# pedal.net
KiCad netlist of a schematic drawn in EAGLE
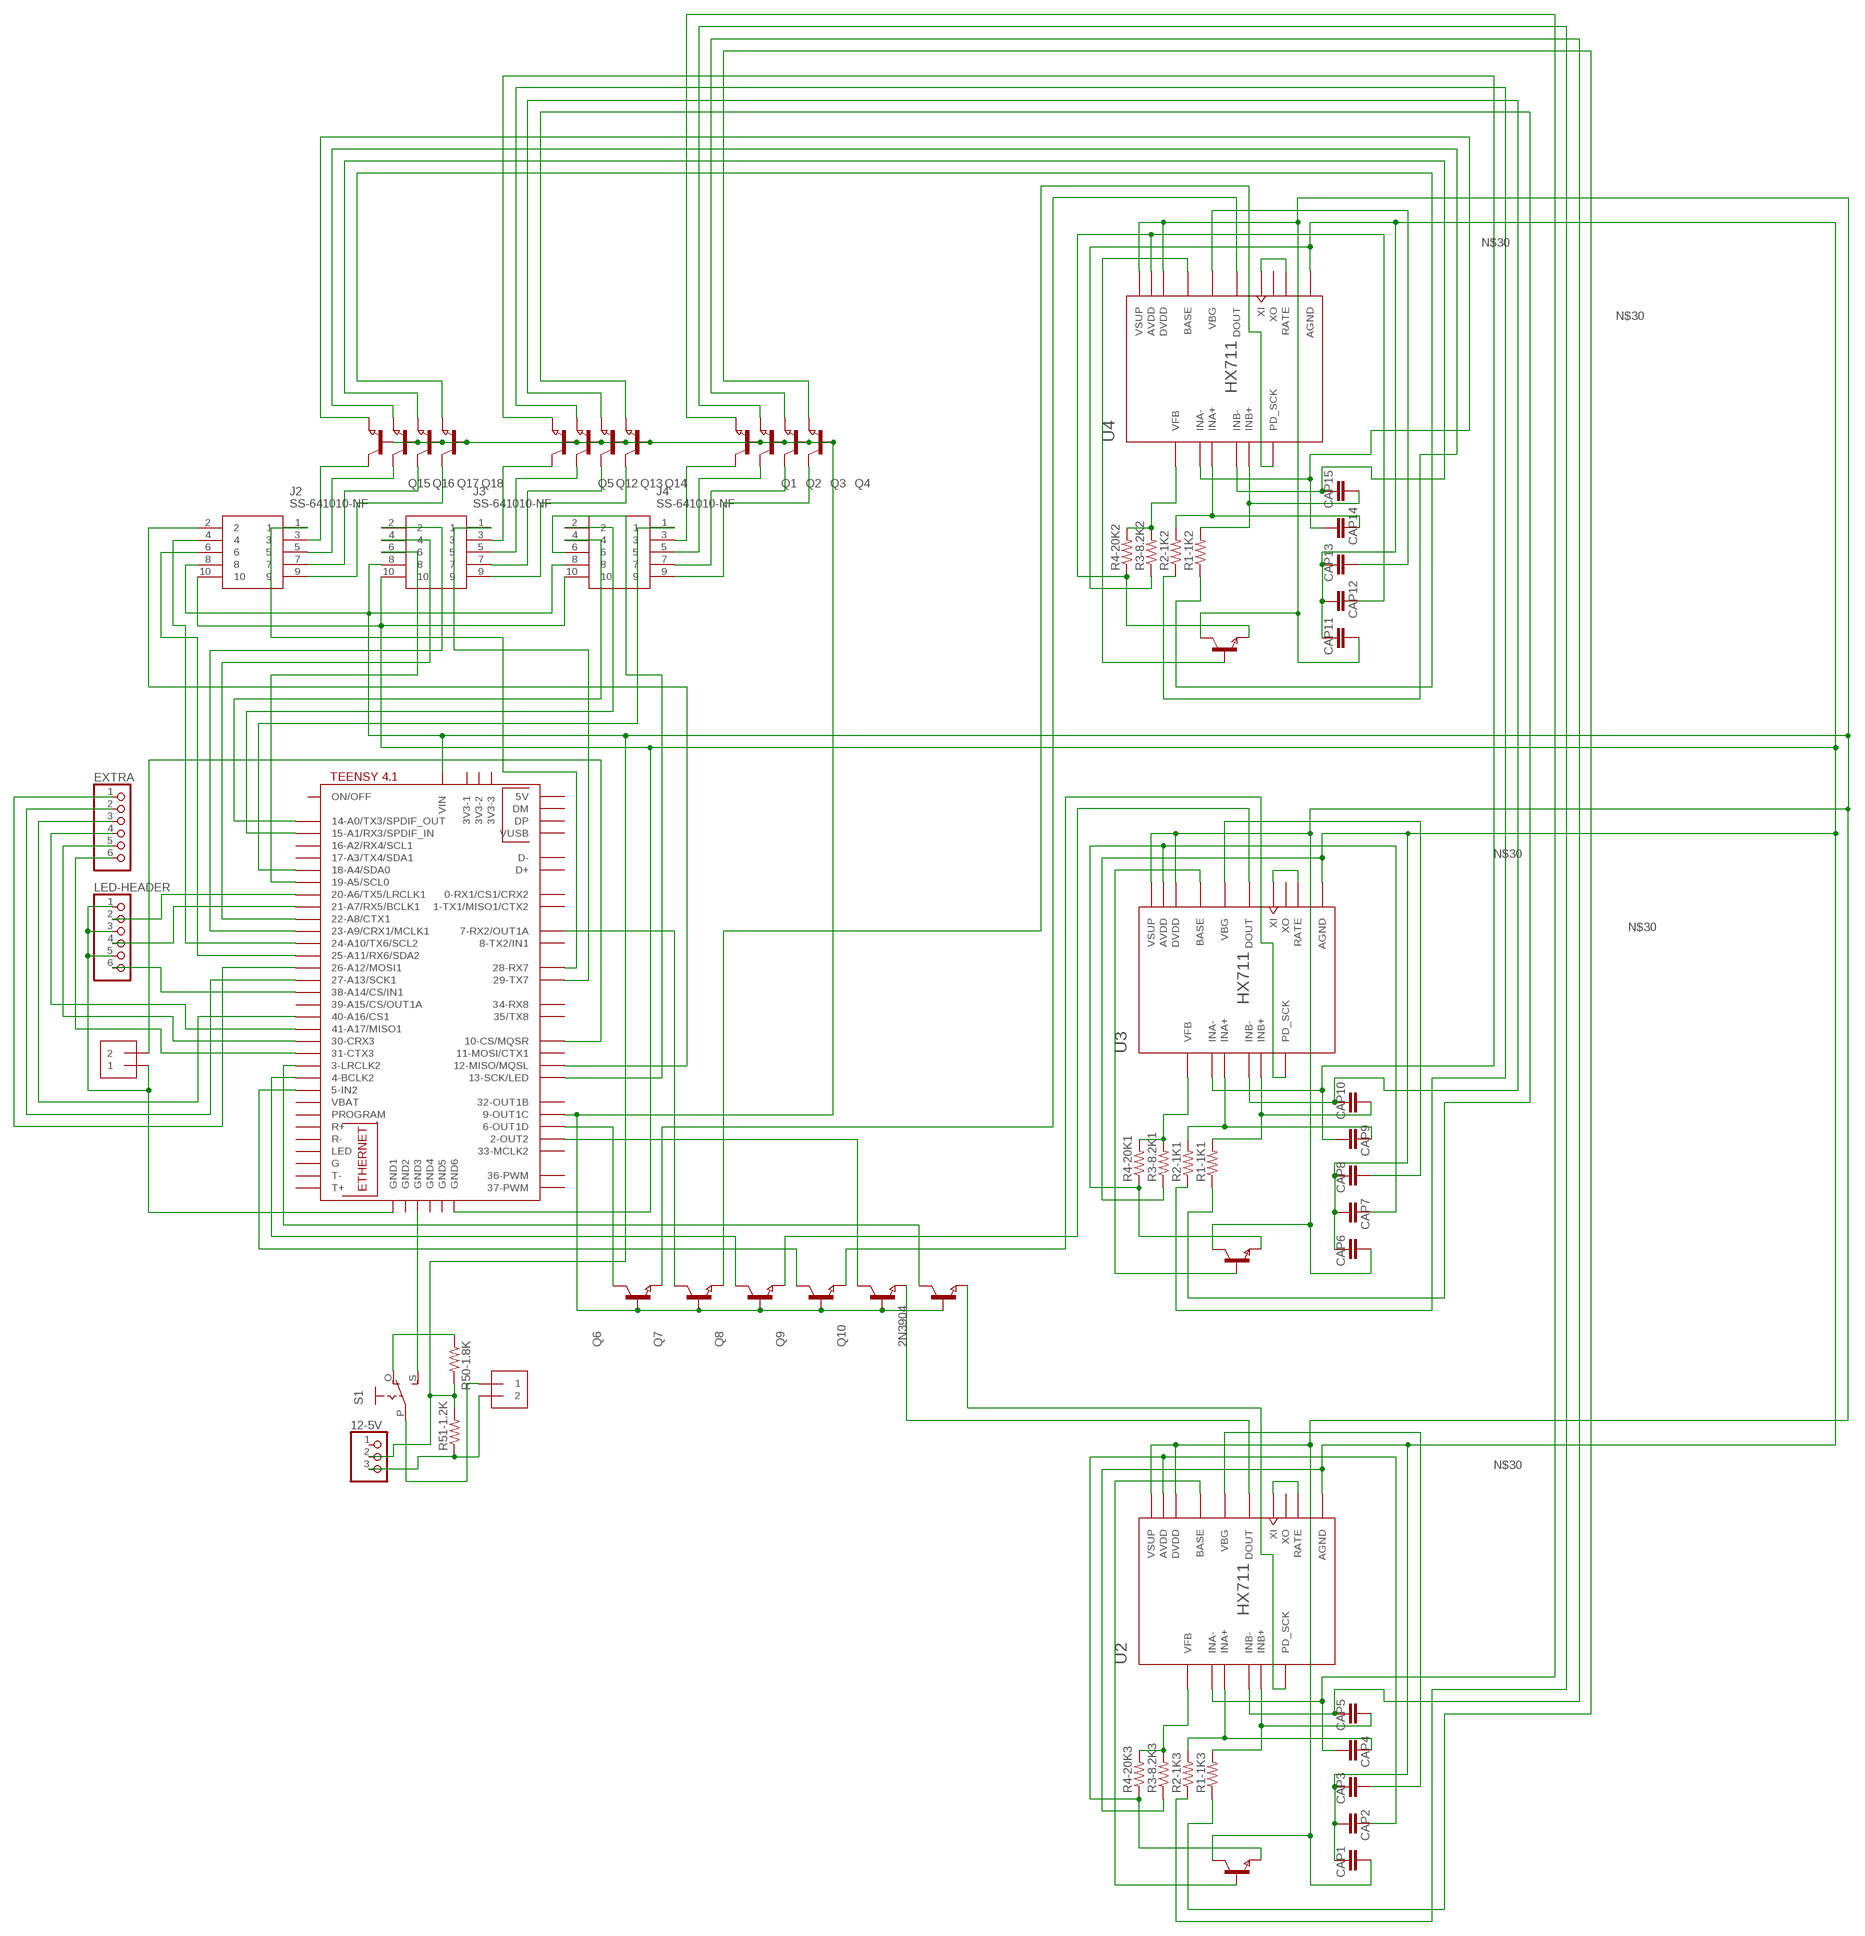
[diagram p0: schematic, sheet 1]

(export (version "E")
  (design (tool "Eeschema 10.0.6"))
  (components
    (comp (ref "2N3904")
      (value "NPN-TRANSISTOR_SOT23")
      (footprint "eagle-import:SOT23")
      (libsource (lib "eagle-import") (part "NPN-TRANSISTOR_SOT23"))
    )
    (comp (ref "12-5V")
      (value "PINHD-1X3")
      (footprint "eagle-import:1X03")
      (libsource (lib "eagle-import") (part "PINHD-1X3"))
    )
    (comp (ref "CAP1")
      (value "1uf")
      (footprint "eagle-import:0603")
      (libsource (lib "eagle-import") (part "10NF-0603-50V-10%"))
    )
    (comp (ref "CAP2")
      (value "1uf")
      (footprint "eagle-import:0603")
      (libsource (lib "eagle-import") (part "10NF-0603-50V-10%"))
    )
    (comp (ref "CAP3")
      (value "1uf")
      (footprint "eagle-import:0603")
      (libsource (lib "eagle-import") (part "10NF-0603-50V-10%"))
    )
    (comp (ref "CAP4")
      (value ".1uf")
      (footprint "eagle-import:0603")
      (libsource (lib "eagle-import") (part "10NF-0603-50V-10%"))
    )
    (comp (ref "CAP5")
      (value ".1uf")
      (footprint "eagle-import:0603")
      (libsource (lib "eagle-import") (part "10NF-0603-50V-10%"))
    )
    (comp (ref "CAP6")
      (value "1uf")
      (footprint "eagle-import:0603")
      (libsource (lib "eagle-import") (part "10NF-0603-50V-10%"))
    )
    (comp (ref "CAP7")
      (value "1uf")
      (footprint "eagle-import:0603")
      (libsource (lib "eagle-import") (part "10NF-0603-50V-10%"))
    )
    (comp (ref "CAP8")
      (value "1uf")
      (footprint "eagle-import:0603")
      (libsource (lib "eagle-import") (part "10NF-0603-50V-10%"))
    )
    (comp (ref "CAP9")
      (value ".1uf")
      (footprint "eagle-import:0603")
      (libsource (lib "eagle-import") (part "10NF-0603-50V-10%"))
    )
    (comp (ref "CAP10")
      (value ".1uf")
      (footprint "eagle-import:0603")
      (libsource (lib "eagle-import") (part "10NF-0603-50V-10%"))
    )
    (comp (ref "CAP11")
      (value "1uf")
      (footprint "eagle-import:0603")
      (libsource (lib "eagle-import") (part "10NF-0603-50V-10%"))
    )
    (comp (ref "CAP12")
      (value "1uf")
      (footprint "eagle-import:0603")
      (libsource (lib "eagle-import") (part "10NF-0603-50V-10%"))
    )
    (comp (ref "CAP13")
      (value "1uf")
      (footprint "eagle-import:0603")
      (libsource (lib "eagle-import") (part "10NF-0603-50V-10%"))
    )
    (comp (ref "CAP14")
      (value ".1uf")
      (footprint "eagle-import:0603")
      (libsource (lib "eagle-import") (part "10NF-0603-50V-10%"))
    )
    (comp (ref "CAP15")
      (value ".1uf")
      (footprint "eagle-import:0603")
      (libsource (lib "eagle-import") (part "10NF-0603-50V-10%"))
    )
    (comp (ref "E-STOP")
      (value "1X2-3.5MM")
      (footprint "eagle-import:1X2-3.5MM")
      (libsource (lib "eagle-import") (part "1X2-3.5MM"))
    )
    (comp (ref "EXTRA")
      (value "PINHD-1X6B")
      (footprint "eagle-import:1X06-BIG")
      (libsource (lib "eagle-import") (part "PINHD-1X6B"))
    )
    (comp (ref "J2")
      (value "SS-641010-NF")
      (footprint "eagle-import:SS-641010-NF")
      (fields (field (name "MOUSER_PART_NUMBER") "530-SS-641010-NF"))
      (libsource (lib "eagle-import") (part "SS-641010-NF"))
    )
    (comp (ref "J3")
      (value "SS-641010-NF")
      (footprint "eagle-import:SS-641010-NF")
      (fields (field (name "MOUSER_PART_NUMBER") "530-SS-641010-NF"))
      (libsource (lib "eagle-import") (part "SS-641010-NF"))
    )
    (comp (ref "J4")
      (value "SS-641010-NF")
      (footprint "eagle-import:SS-641010-NF")
      (fields (field (name "MOUSER_PART_NUMBER") "530-SS-641010-NF"))
      (libsource (lib "eagle-import") (part "SS-641010-NF"))
    )
    (comp (ref "LED-HEADER")
      (value "PINHD-1X6B")
      (footprint "eagle-import:1X06-BIG")
      (libsource (lib "eagle-import") (part "PINHD-1X6B"))
    )
    (comp (ref "POWER-IN")
      (value "1X2-3.5MM")
      (footprint "eagle-import:1X2-3.5MM")
      (libsource (lib "eagle-import") (part "1X2-3.5MM"))
    )
    (comp (ref "Q1")
      (value "NPN-TRANSISTOR_SOT23")
      (footprint "eagle-import:SOT23")
      (libsource (lib "eagle-import") (part "NPN-TRANSISTOR_SOT23"))
    )
    (comp (ref "Q2")
      (value "NPN-TRANSISTOR_SOT23")
      (footprint "eagle-import:SOT23")
      (libsource (lib "eagle-import") (part "NPN-TRANSISTOR_SOT23"))
    )
    (comp (ref "Q3")
      (value "NPN-TRANSISTOR_SOT23")
      (footprint "eagle-import:SOT23")
      (libsource (lib "eagle-import") (part "NPN-TRANSISTOR_SOT23"))
    )
    (comp (ref "Q4")
      (value "NPN-TRANSISTOR_SOT23")
      (footprint "eagle-import:SOT23")
      (libsource (lib "eagle-import") (part "NPN-TRANSISTOR_SOT23"))
    )
    (comp (ref "Q5")
      (value "NPN-TRANSISTOR_SOT23")
      (footprint "eagle-import:SOT23")
      (libsource (lib "eagle-import") (part "NPN-TRANSISTOR_SOT23"))
    )
    (comp (ref "Q6")
      (value "NPN-TRANSISTOR_SOT23")
      (footprint "eagle-import:SOT23")
      (libsource (lib "eagle-import") (part "NPN-TRANSISTOR_SOT23"))
    )
    (comp (ref "Q7")
      (value "NPN-TRANSISTOR_SOT23")
      (footprint "eagle-import:SOT23")
      (libsource (lib "eagle-import") (part "NPN-TRANSISTOR_SOT23"))
    )
    (comp (ref "Q8")
      (value "NPN-TRANSISTOR_SOT23")
      (footprint "eagle-import:SOT23")
      (libsource (lib "eagle-import") (part "NPN-TRANSISTOR_SOT23"))
    )
    (comp (ref "Q9")
      (value "NPN-TRANSISTOR_SOT23")
      (footprint "eagle-import:SOT23")
      (libsource (lib "eagle-import") (part "NPN-TRANSISTOR_SOT23"))
    )
    (comp (ref "Q10")
      (value "NPN-TRANSISTOR_SOT23")
      (footprint "eagle-import:SOT23")
      (libsource (lib "eagle-import") (part "NPN-TRANSISTOR_SOT23"))
    )
    (comp (ref "Q12")
      (value "NPN-TRANSISTOR_SOT23")
      (footprint "eagle-import:SOT23")
      (libsource (lib "eagle-import") (part "NPN-TRANSISTOR_SOT23"))
    )
    (comp (ref "Q13")
      (value "NPN-TRANSISTOR_SOT23")
      (footprint "eagle-import:SOT23")
      (libsource (lib "eagle-import") (part "NPN-TRANSISTOR_SOT23"))
    )
    (comp (ref "Q14")
      (value "NPN-TRANSISTOR_SOT23")
      (footprint "eagle-import:SOT23")
      (libsource (lib "eagle-import") (part "NPN-TRANSISTOR_SOT23"))
    )
    (comp (ref "Q15")
      (value "NPN-TRANSISTOR_SOT23")
      (footprint "eagle-import:SOT23")
      (libsource (lib "eagle-import") (part "NPN-TRANSISTOR_SOT23"))
    )
    (comp (ref "Q16")
      (value "NPN-TRANSISTOR_SOT23")
      (footprint "eagle-import:SOT23")
      (libsource (lib "eagle-import") (part "NPN-TRANSISTOR_SOT23"))
    )
    (comp (ref "Q17")
      (value "NPN-TRANSISTOR_SOT23")
      (footprint "eagle-import:SOT23")
      (libsource (lib "eagle-import") (part "NPN-TRANSISTOR_SOT23"))
    )
    (comp (ref "Q18")
      (value "NPN-TRANSISTOR_SOT23")
      (footprint "eagle-import:SOT23")
      (libsource (lib "eagle-import") (part "NPN-TRANSISTOR_SOT23"))
    )
    (comp (ref "R1-1K1")
      (value "R-US_R0603")
      (footprint "eagle-import:R0603")
      (libsource (lib "eagle-import") (part "R-US_R0603"))
    )
    (comp (ref "R1-1K2")
      (value "R-US_R0603")
      (footprint "eagle-import:R0603")
      (libsource (lib "eagle-import") (part "R-US_R0603"))
    )
    (comp (ref "R1-1K3")
      (value "R-US_R0603")
      (footprint "eagle-import:R0603")
      (libsource (lib "eagle-import") (part "R-US_R0603"))
    )
    (comp (ref "R2-1K1")
      (value "R-US_R0603")
      (footprint "eagle-import:R0603")
      (libsource (lib "eagle-import") (part "R-US_R0603"))
    )
    (comp (ref "R2-1K2")
      (value "R-US_R0603")
      (footprint "eagle-import:R0603")
      (libsource (lib "eagle-import") (part "R-US_R0603"))
    )
    (comp (ref "R2-1K3")
      (value "R-US_R0603")
      (footprint "eagle-import:R0603")
      (libsource (lib "eagle-import") (part "R-US_R0603"))
    )
    (comp (ref "R3-8.2K1")
      (value "R-US_R0603")
      (footprint "eagle-import:R0603")
      (libsource (lib "eagle-import") (part "R-US_R0603"))
    )
    (comp (ref "R3-8.2K2")
      (value "R-US_R0603")
      (footprint "eagle-import:R0603")
      (libsource (lib "eagle-import") (part "R-US_R0603"))
    )
    (comp (ref "R3-8.2K3")
      (value "R-US_R0603")
      (footprint "eagle-import:R0603")
      (libsource (lib "eagle-import") (part "R-US_R0603"))
    )
    (comp (ref "R4-20K1")
      (value "R-US_R0603")
      (footprint "eagle-import:R0603")
      (libsource (lib "eagle-import") (part "R-US_R0603"))
    )
    (comp (ref "R4-20K2")
      (value "R-US_R0603")
      (footprint "eagle-import:R0603")
      (libsource (lib "eagle-import") (part "R-US_R0603"))
    )
    (comp (ref "R4-20K3")
      (value "R-US_R0603")
      (footprint "eagle-import:R0603")
      (libsource (lib "eagle-import") (part "R-US_R0603"))
    )
    (comp (ref "R50-1.8K")
      (value "R-US_R0603")
      (footprint "eagle-import:R0603")
      (libsource (lib "eagle-import") (part "R-US_R0603"))
    )
    (comp (ref "R51-1.2K")
      (value "R-US_R0603")
      (footprint "eagle-import:R0603")
      (libsource (lib "eagle-import") (part "R-US_R0603"))
    )
    (comp (ref "S1")
      (value "EG1218S")
      (footprint "eagle-import:EG1218")
      (libsource (lib "eagle-import") (part "EG1218S"))
    )
    (comp (ref "T1")
      (value "8550")
      (footprint "eagle-import:SOT-23")
      (libsource (lib "eagle-import") (part "FMMT451"))
    )
    (comp (ref "T2")
      (value "8550")
      (footprint "eagle-import:SOT-23")
      (libsource (lib "eagle-import") (part "FMMT451"))
    )
    (comp (ref "T3")
      (value "8550")
      (footprint "eagle-import:SOT-23")
      (libsource (lib "eagle-import") (part "FMMT451"))
    )
    (comp (ref "U$5")
      (value "TEENSY41")
      (footprint "eagle-import:TEENSY41")
      (libsource (lib "eagle-import") (part "TEENSY41"))
    )
    (comp (ref "U2")
      (value "HX711")
      (footprint "eagle-import:SOP127P600X180-16N")
      (fields (field (name "MF") "AVIA SEMICONDUCTOR"))
      (libsource (lib "eagle-import") (part "HX711"))
    )
    (comp (ref "U3")
      (value "HX711")
      (footprint "eagle-import:SOP127P600X180-16N")
      (fields (field (name "MF") "AVIA SEMICONDUCTOR"))
      (libsource (lib "eagle-import") (part "HX711"))
    )
    (comp (ref "U4")
      (value "HX711")
      (footprint "eagle-import:SOP127P600X180-16N")
      (fields (field (name "MF") "AVIA SEMICONDUCTOR"))
      (libsource (lib "eagle-import") (part "HX711"))
    )
  )
  (nets
    (net (code "1") (name "/N$30") (class "Default")
      (node (ref "CAP1") (pin "1") (pinfunction "1_1") (pintype "passive"))
      (node (ref "CAP11") (pin "1") (pinfunction "1_1") (pintype "passive"))
      (node (ref "CAP12") (pin "1") (pinfunction "1_1") (pintype "passive"))
      (node (ref "CAP13") (pin "1") (pinfunction "1_1") (pintype "passive"))
      (node (ref "CAP2") (pin "1") (pinfunction "1_1") (pintype "passive"))
      (node (ref "CAP3") (pin "1") (pinfunction "1_1") (pintype "passive"))
      (node (ref "CAP6") (pin "1") (pinfunction "1_1") (pintype "passive"))
      (node (ref "CAP7") (pin "1") (pinfunction "1_1") (pintype "passive"))
      (node (ref "CAP8") (pin "1") (pinfunction "1_1") (pintype "passive"))
      (node (ref "J2") (pin "10") (pinfunction "10_10") (pintype "bidirectional"))
      (node (ref "J3") (pin "10") (pinfunction "10_10") (pintype "bidirectional"))
      (node (ref "J4") (pin "10") (pinfunction "10_10") (pintype "bidirectional"))
      (node (ref "R3-8.2K1") (pin "1") (pinfunction "1_1") (pintype "passive"))
      (node (ref "R3-8.2K2") (pin "1") (pinfunction "1_1") (pintype "passive"))
      (node (ref "R3-8.2K3") (pin "1") (pinfunction "1_1") (pintype "passive"))
      (node (ref "U$5") (pin "GND6") (pinfunction "GND6_GND6") (pintype "bidirectional"))
      (node (ref "U2") (pin "5") (pinfunction "AGND_5") (pintype "power_in"))
      (node (ref "U3") (pin "5") (pinfunction "AGND_5") (pintype "power_in"))
      (node (ref "U4") (pin "5") (pinfunction "AGND_5") (pintype "power_in"))
    )
    (net (code "2") (name "Net-(2N3904-B)") (class "Default")
      (node (ref "2N3904") (pin "1") (pinfunction "B_1") (pintype "passive"))
      (node (ref "Q1") (pin "1") (pinfunction "B_1") (pintype "passive"))
      (node (ref "Q10") (pin "1") (pinfunction "B_1") (pintype "passive"))
      (node (ref "Q12") (pin "1") (pinfunction "B_1") (pintype "passive"))
      (node (ref "Q13") (pin "1") (pinfunction "B_1") (pintype "passive"))
      (node (ref "Q14") (pin "1") (pinfunction "B_1") (pintype "passive"))
      (node (ref "Q15") (pin "1") (pinfunction "B_1") (pintype "passive"))
      (node (ref "Q16") (pin "1") (pinfunction "B_1") (pintype "passive"))
      (node (ref "Q17") (pin "1") (pinfunction "B_1") (pintype "passive"))
      (node (ref "Q18") (pin "1") (pinfunction "B_1") (pintype "passive"))
      (node (ref "Q2") (pin "1") (pinfunction "B_1") (pintype "passive"))
      (node (ref "Q3") (pin "1") (pinfunction "B_1") (pintype "passive"))
      (node (ref "Q4") (pin "1") (pinfunction "B_1") (pintype "passive"))
      (node (ref "Q5") (pin "1") (pinfunction "B_1") (pintype "passive"))
      (node (ref "Q6") (pin "1") (pinfunction "B_1") (pintype "passive"))
      (node (ref "Q7") (pin "1") (pinfunction "B_1") (pintype "passive"))
      (node (ref "Q8") (pin "1") (pinfunction "B_1") (pintype "passive"))
      (node (ref "Q9") (pin "1") (pinfunction "B_1") (pintype "passive"))
      (node (ref "U$5") (pin "9-OUT1C") (pinfunction "9-OUT1C_9-OUT1C") (pintype "bidirectional"))
    )
    (net (code "3") (name "Net-(2N3904-C)") (class "Default")
      (node (ref "2N3904") (pin "3") (pinfunction "C_3") (pintype "passive"))
      (node (ref "U$5") (pin "3-LRCLK2") (pinfunction "3-LRCLK2_3-LRCLK2") (pintype "bidirectional"))
    )
    (net (code "4") (name "Net-(2N3904-E)") (class "Default")
      (node (ref "2N3904") (pin "2") (pinfunction "E_2") (pintype "passive"))
      (node (ref "U2") (pin "11") (pinfunction "PD_SCK_11") (pintype "input"))
    )
    (net (code "5") (name "Net-(12-5V-Pad3)") (class "Default")
      (node (ref "12-5V") (pin "3") (pinfunction "3_3") (pintype "passive"))
      (node (ref "POWER-IN") (pin "2") (pinfunction "2_2") (pintype "passive"))
      (node (ref "R51-1.2K") (pin "1") (pinfunction "1_1") (pintype "passive"))
    )
    (net (code "6") (name "Net-(E-STOP-Pad1)") (class "Default")
      (node (ref "E-STOP") (pin "1") (pinfunction "1_1") (pintype "passive"))
      (node (ref "LED-HEADER") (pin "1") (pinfunction "1_1") (pintype "passive"))
      (node (ref "LED-HEADER") (pin "3") (pinfunction "3_3") (pintype "passive"))
      (node (ref "LED-HEADER") (pin "5") (pinfunction "5_5") (pintype "passive"))
      (node (ref "U$5") (pin "GND1") (pinfunction "GND1_GND1") (pintype "bidirectional"))
    )
    (net (code "7") (name "Net-(EXTRA-Pad1)") (class "Default")
      (node (ref "EXTRA") (pin "1") (pinfunction "1_1") (pintype "passive"))
      (node (ref "U$5") (pin "26-A12/MOSI1") (pinfunction "26-A12/MOSI1_26-A12/MOSI1") (pintype "bidirectional"))
    )
    (net (code "8") (name "Net-(EXTRA-Pad2)") (class "Default")
      (node (ref "EXTRA") (pin "2") (pinfunction "2_2") (pintype "passive"))
      (node (ref "U$5") (pin "27-A13/SCK1") (pinfunction "27-A13/SCK1_27-A13/SCK1") (pintype "bidirectional"))
    )
    (net (code "9") (name "Net-(EXTRA-Pad3)") (class "Default")
      (node (ref "EXTRA") (pin "3") (pinfunction "3_3") (pintype "passive"))
      (node (ref "U$5") (pin "40-A16/CS1") (pinfunction "40-A16/CS1_40-A16/CS1") (pintype "bidirectional"))
    )
    (net (code "10") (name "Net-(EXTRA-Pad4)") (class "Default")
      (node (ref "EXTRA") (pin "4") (pinfunction "4_4") (pintype "passive"))
      (node (ref "U$5") (pin "41-A17/MISO1") (pinfunction "41-A17/MISO1_41-A17/MISO1") (pintype "bidirectional"))
    )
    (net (code "11") (name "Net-(EXTRA-Pad5)") (class "Default")
      (node (ref "EXTRA") (pin "5") (pinfunction "5_5") (pintype "passive"))
      (node (ref "U$5") (pin "30-CRX3") (pinfunction "30-CRX3_30-CRX3") (pintype "bidirectional"))
    )
    (net (code "12") (name "Net-(EXTRA-Pad6)") (class "Default")
      (node (ref "EXTRA") (pin "6") (pinfunction "6_6") (pintype "passive"))
      (node (ref "U$5") (pin "31-CTX3") (pinfunction "31-CTX3_31-CTX3") (pintype "bidirectional"))
    )
    (net (code "13") (name "Net-(J2-Pad1)") (class "Default")
      (node (ref "J2") (pin "1") (pinfunction "1_1") (pintype "bidirectional"))
      (node (ref "U$5") (pin "28-RX7") (pinfunction "28-RX7_28-RX7") (pintype "bidirectional"))
    )
    (net (code "14") (name "Net-(J2-Pad2)") (class "Default")
      (node (ref "J2") (pin "2") (pinfunction "2_2") (pintype "bidirectional"))
      (node (ref "U$5") (pin "12-MISO/MQSL") (pinfunction "12-MISO/MQSL_12-MISO/MQSL") (pintype "bidirectional"))
    )
    (net (code "15") (name "Net-(J2-Pad4)") (class "Default")
      (node (ref "J2") (pin "4") (pinfunction "4_4") (pintype "bidirectional"))
      (node (ref "U$5") (pin "24-A10/TX6/SCL2") (pinfunction "24-A10/TX6/SCL2_24-A10/TX6/SCL2") (pintype "bidirectional"))
    )
    (net (code "16") (name "Net-(J2-Pad6)") (class "Default")
      (node (ref "J2") (pin "6") (pinfunction "6_6") (pintype "bidirectional"))
      (node (ref "U$5") (pin "25-A11/RX6/SDA2") (pinfunction "25-A11/RX6/SDA2_25-A11/RX6/SDA2") (pintype "bidirectional"))
    )
    (net (code "17") (name "Net-(J3-Pad1)") (class "Default")
      (node (ref "J3") (pin "1") (pinfunction "1_1") (pintype "bidirectional"))
      (node (ref "U$5") (pin "29-TX7") (pinfunction "29-TX7_29-TX7") (pintype "bidirectional"))
    )
    (net (code "18") (name "Net-(J3-Pad2)") (class "Default")
      (node (ref "J3") (pin "2") (pinfunction "2_2") (pintype "bidirectional"))
      (node (ref "U$5") (pin "23-A9/CRX1/MCLK1") (pinfunction "23-A9/CRX1/MCLK1_23-A9/CRX1/MCLK1") (pintype "bidirectional"))
    )
    (net (code "19") (name "Net-(J3-Pad4)") (class "Default")
      (node (ref "J3") (pin "4") (pinfunction "4_4") (pintype "bidirectional"))
      (node (ref "U$5") (pin "22-A8/CTX1") (pinfunction "22-A8/CTX1_22-A8/CTX1") (pintype "bidirectional"))
    )
    (net (code "20") (name "Net-(J3-Pad6)") (class "Default")
      (node (ref "J3") (pin "6") (pinfunction "6_6") (pintype "bidirectional"))
      (node (ref "U$5") (pin "19-A5/SCL0") (pinfunction "19-A5/SCL0_19-A5/SCL0") (pintype "bidirectional"))
    )
    (net (code "21") (name "Net-(J4-Pad1)") (class "Default")
      (node (ref "J4") (pin "1") (pinfunction "1_1") (pintype "bidirectional"))
      (node (ref "U$5") (pin "18-A4/SDA0") (pinfunction "18-A4/SDA0_18-A4/SDA0") (pintype "bidirectional"))
    )
    (net (code "22") (name "Net-(J4-Pad2)") (class "Default")
      (node (ref "J4") (pin "2") (pinfunction "2_2") (pintype "bidirectional"))
      (node (ref "U$5") (pin "15-A1/RX3/SPDIF_IN") (pinfunction "15-A1/RX3/SPDIF_IN_15-A1/RX3/SPDIF_IN") (pintype "bidirectional"))
    )
    (net (code "23") (name "Net-(J4-Pad4)") (class "Default")
      (node (ref "J4") (pin "4") (pinfunction "4_4") (pintype "bidirectional"))
      (node (ref "U$5") (pin "14-A0/TX3/SPDIF_OUT") (pinfunction "14-A0/TX3/SPDIF_OUT_14-A0/TX3/SPDIF_OUT") (pintype "bidirectional"))
    )
    (net (code "24") (name "Net-(J4-Pad6)") (class "Default")
      (node (ref "J4") (pin "6") (pinfunction "6_6") (pintype "bidirectional"))
      (node (ref "U$5") (pin "13-SCK/LED") (pinfunction "13-SCK/LED_13-SCK/LED") (pintype "bidirectional"))
    )
    (net (code "25") (name "Net-(LED-HEADER-Pad2)") (class "Default")
      (node (ref "LED-HEADER") (pin "2") (pinfunction "2_2") (pintype "passive"))
      (node (ref "U$5") (pin "20-A6/TX5/LRCLK1") (pinfunction "20-A6/TX5/LRCLK1_20-A6/TX5/LRCLK1") (pintype "bidirectional"))
    )
    (net (code "26") (name "Net-(LED-HEADER-Pad4)") (class "Default")
      (node (ref "LED-HEADER") (pin "4") (pinfunction "4_4") (pintype "passive"))
      (node (ref "U$5") (pin "21-A7/RX5/BCLK1") (pinfunction "21-A7/RX5/BCLK1_21-A7/RX5/BCLK1") (pintype "bidirectional"))
    )
    (net (code "27") (name "Net-(LED-HEADER-Pad6)") (class "Default")
      (node (ref "LED-HEADER") (pin "6") (pinfunction "6_6") (pintype "passive"))
      (node (ref "U$5") (pin "38-A14/CS/IN1") (pinfunction "38-A14/CS/IN1_38-A14/CS/IN1") (pintype "bidirectional"))
    )
    (net (code "28") (name "Net-(POWER-IN-Pad1)") (class "Default")
      (node (ref "POWER-IN") (pin "1") (pinfunction "1_1") (pintype "passive"))
      (node (ref "S1") (pin "P") (pinfunction "P_P") (pintype "passive"))
    )
    (net (code "29") (name "Net-(Q1-C)") (class "Default")
      (node (ref "J4") (pin "3") (pinfunction "3_3") (pintype "bidirectional"))
      (node (ref "Q1") (pin "3") (pinfunction "C_3") (pintype "passive"))
    )
    (net (code "30") (name "Net-(Q1-E)") (class "Default")
      (node (ref "CAP4") (pin "1") (pinfunction "1_1") (pintype "passive"))
      (node (ref "Q1") (pin "2") (pinfunction "E_2") (pintype "passive"))
      (node (ref "U2") (pin "7") (pinfunction "INA-_7") (pintype "input"))
    )
    (net (code "31") (name "Net-(Q2-C)") (class "Default")
      (node (ref "J4") (pin "5") (pinfunction "5_5") (pintype "bidirectional"))
      (node (ref "Q2") (pin "3") (pinfunction "C_3") (pintype "passive"))
    )
    (net (code "32") (name "Net-(Q2-E)") (class "Default")
      (node (ref "Q2") (pin "2") (pinfunction "E_2") (pintype "passive"))
      (node (ref "R2-1K3") (pin "1") (pinfunction "1_1") (pintype "passive"))
    )
    (net (code "33") (name "Net-(Q3-C)") (class "Default")
      (node (ref "J4") (pin "7") (pinfunction "7_7") (pintype "bidirectional"))
      (node (ref "Q3") (pin "3") (pinfunction "C_3") (pintype "passive"))
    )
    (net (code "34") (name "Net-(Q3-E)") (class "Default")
      (node (ref "CAP5") (pin "1") (pinfunction "1_1") (pintype "passive"))
      (node (ref "Q3") (pin "2") (pinfunction "E_2") (pintype "passive"))
      (node (ref "U2") (pin "9") (pinfunction "INB-_9") (pintype "input"))
    )
    (net (code "35") (name "Net-(Q4-C)") (class "Default")
      (node (ref "J4") (pin "9") (pinfunction "9_9") (pintype "bidirectional"))
      (node (ref "Q4") (pin "3") (pinfunction "C_3") (pintype "passive"))
    )
    (net (code "36") (name "Net-(Q4-E)") (class "Default")
      (node (ref "Q4") (pin "2") (pinfunction "E_2") (pintype "passive"))
      (node (ref "R1-1K3") (pin "1") (pinfunction "1_1") (pintype "passive"))
    )
    (net (code "37") (name "Net-(Q5-C)") (class "Default")
      (node (ref "J3") (pin "3") (pinfunction "3_3") (pintype "bidirectional"))
      (node (ref "Q5") (pin "3") (pinfunction "C_3") (pintype "passive"))
    )
    (net (code "38") (name "Net-(Q5-E)") (class "Default")
      (node (ref "CAP9") (pin "1") (pinfunction "1_1") (pintype "passive"))
      (node (ref "Q5") (pin "2") (pinfunction "E_2") (pintype "passive"))
      (node (ref "U3") (pin "7") (pinfunction "INA-_7") (pintype "input"))
    )
    (net (code "39") (name "Net-(Q6-C)") (class "Default")
      (node (ref "Q6") (pin "3") (pinfunction "C_3") (pintype "passive"))
      (node (ref "U$5") (pin "6-OUT1D") (pinfunction "6-OUT1D_6-OUT1D") (pintype "bidirectional"))
    )
    (net (code "40") (name "Net-(Q6-E)") (class "Default")
      (node (ref "Q6") (pin "2") (pinfunction "E_2") (pintype "passive"))
      (node (ref "U4") (pin "12") (pinfunction "DOUT_12") (pintype "output"))
    )
    (net (code "41") (name "Net-(Q7-C)") (class "Default")
      (node (ref "Q7") (pin "3") (pinfunction "C_3") (pintype "passive"))
      (node (ref "U$5") (pin "7-RX2/OUT1A") (pinfunction "7-RX2/OUT1A_7-RX2/OUT1A") (pintype "bidirectional"))
    )
    (net (code "42") (name "Net-(Q7-E)") (class "Default")
      (node (ref "Q7") (pin "2") (pinfunction "E_2") (pintype "passive"))
      (node (ref "U4") (pin "11") (pinfunction "PD_SCK_11") (pintype "input"))
    )
    (net (code "43") (name "Net-(Q8-C)") (class "Default")
      (node (ref "Q8") (pin "3") (pinfunction "C_3") (pintype "passive"))
      (node (ref "U$5") (pin "4-BCLK2") (pinfunction "4-BCLK2_4-BCLK2") (pintype "bidirectional"))
    )
    (net (code "44") (name "Net-(Q8-E)") (class "Default")
      (node (ref "Q8") (pin "2") (pinfunction "E_2") (pintype "passive"))
      (node (ref "U3") (pin "12") (pinfunction "DOUT_12") (pintype "output"))
    )
    (net (code "45") (name "Net-(Q9-C)") (class "Default")
      (node (ref "Q9") (pin "3") (pinfunction "C_3") (pintype "passive"))
      (node (ref "U$5") (pin "5-IN2") (pinfunction "5-IN2_5-IN2") (pintype "bidirectional"))
    )
    (net (code "46") (name "Net-(Q9-E)") (class "Default")
      (node (ref "Q9") (pin "2") (pinfunction "E_2") (pintype "passive"))
      (node (ref "U3") (pin "11") (pinfunction "PD_SCK_11") (pintype "input"))
    )
    (net (code "47") (name "Net-(Q10-C)") (class "Default")
      (node (ref "Q10") (pin "3") (pinfunction "C_3") (pintype "passive"))
      (node (ref "U$5") (pin "2-OUT2") (pinfunction "2-OUT2_2-OUT2") (pintype "bidirectional"))
    )
    (net (code "48") (name "Net-(Q10-E)") (class "Default")
      (node (ref "Q10") (pin "2") (pinfunction "E_2") (pintype "passive"))
      (node (ref "U2") (pin "12") (pinfunction "DOUT_12") (pintype "output"))
    )
    (net (code "49") (name "Net-(Q12-C)") (class "Default")
      (node (ref "J3") (pin "5") (pinfunction "5_5") (pintype "bidirectional"))
      (node (ref "Q12") (pin "3") (pinfunction "C_3") (pintype "passive"))
    )
    (net (code "50") (name "Net-(Q12-E)") (class "Default")
      (node (ref "Q12") (pin "2") (pinfunction "E_2") (pintype "passive"))
      (node (ref "R2-1K1") (pin "1") (pinfunction "1_1") (pintype "passive"))
    )
    (net (code "51") (name "Net-(Q13-C)") (class "Default")
      (node (ref "J3") (pin "7") (pinfunction "7_7") (pintype "bidirectional"))
      (node (ref "Q13") (pin "3") (pinfunction "C_3") (pintype "passive"))
    )
    (net (code "52") (name "Net-(Q13-E)") (class "Default")
      (node (ref "CAP10") (pin "1") (pinfunction "1_1") (pintype "passive"))
      (node (ref "Q13") (pin "2") (pinfunction "E_2") (pintype "passive"))
      (node (ref "U3") (pin "9") (pinfunction "INB-_9") (pintype "input"))
    )
    (net (code "53") (name "Net-(Q14-C)") (class "Default")
      (node (ref "J3") (pin "9") (pinfunction "9_9") (pintype "bidirectional"))
      (node (ref "Q14") (pin "3") (pinfunction "C_3") (pintype "passive"))
    )
    (net (code "54") (name "Net-(Q14-E)") (class "Default")
      (node (ref "Q14") (pin "2") (pinfunction "E_2") (pintype "passive"))
      (node (ref "R1-1K1") (pin "1") (pinfunction "1_1") (pintype "passive"))
    )
    (net (code "55") (name "Net-(Q15-C)") (class "Default")
      (node (ref "J2") (pin "3") (pinfunction "3_3") (pintype "bidirectional"))
      (node (ref "Q15") (pin "3") (pinfunction "C_3") (pintype "passive"))
    )
    (net (code "56") (name "Net-(Q15-E)") (class "Default")
      (node (ref "CAP14") (pin "1") (pinfunction "1_1") (pintype "passive"))
      (node (ref "Q15") (pin "2") (pinfunction "E_2") (pintype "passive"))
      (node (ref "U4") (pin "7") (pinfunction "INA-_7") (pintype "input"))
    )
    (net (code "57") (name "Net-(Q16-C)") (class "Default")
      (node (ref "J2") (pin "5") (pinfunction "5_5") (pintype "bidirectional"))
      (node (ref "Q16") (pin "3") (pinfunction "C_3") (pintype "passive"))
    )
    (net (code "58") (name "Net-(Q16-E)") (class "Default")
      (node (ref "Q16") (pin "2") (pinfunction "E_2") (pintype "passive"))
      (node (ref "R2-1K2") (pin "1") (pinfunction "1_1") (pintype "passive"))
    )
    (net (code "59") (name "Net-(Q17-C)") (class "Default")
      (node (ref "J2") (pin "7") (pinfunction "7_7") (pintype "bidirectional"))
      (node (ref "Q17") (pin "3") (pinfunction "C_3") (pintype "passive"))
    )
    (net (code "60") (name "Net-(Q17-E)") (class "Default")
      (node (ref "CAP15") (pin "1") (pinfunction "1_1") (pintype "passive"))
      (node (ref "Q17") (pin "2") (pinfunction "E_2") (pintype "passive"))
      (node (ref "U4") (pin "9") (pinfunction "INB-_9") (pintype "input"))
    )
    (net (code "61") (name "Net-(Q18-C)") (class "Default")
      (node (ref "J2") (pin "9") (pinfunction "9_9") (pintype "bidirectional"))
      (node (ref "Q18") (pin "3") (pinfunction "C_3") (pintype "passive"))
    )
    (net (code "62") (name "Net-(Q18-E)") (class "Default")
      (node (ref "Q18") (pin "2") (pinfunction "E_2") (pintype "passive"))
      (node (ref "R1-1K2") (pin "1") (pinfunction "1_1") (pintype "passive"))
    )
    (net (code "63") (name "Net-(R50-1.8K-Pad1)") (class "Default")
      (node (ref "R50-1.8K") (pin "1") (pinfunction "1_1") (pintype "passive"))
      (node (ref "S1") (pin "O") (pinfunction "O_O") (pintype "passive"))
    )
    (net (code "64") (name "Net-(S1-PadS)") (class "Default")
      (node (ref "S1") (pin "S") (pinfunction "S_S") (pintype "passive"))
      (node (ref "U$5") (pin "GND3") (pinfunction "GND3_GND3") (pintype "bidirectional"))
    )
    (net (code "65") (name "Net-(T1-B)") (class "Default")
      (node (ref "T1") (pin "3") (pinfunction "B_3") (pintype "passive"))
      (node (ref "U2") (pin "2") (pinfunction "BASE_2") (pintype "output"))
    )
    (net (code "66") (name "Net-(T1-C)") (class "Default")
      (node (ref "12-5V") (pin "2") (pinfunction "2_2") (pintype "passive"))
      (node (ref "CAP1") (pin "2") (pinfunction "2_2") (pintype "passive"))
      (node (ref "CAP11") (pin "2") (pinfunction "2_2") (pintype "passive"))
      (node (ref "CAP6") (pin "2") (pinfunction "2_2") (pintype "passive"))
      (node (ref "J2") (pin "8") (pinfunction "8_8") (pintype "bidirectional"))
      (node (ref "J3") (pin "8") (pinfunction "8_8") (pintype "bidirectional"))
      (node (ref "J4") (pin "8") (pinfunction "8_8") (pintype "bidirectional"))
      (node (ref "R50-1.8K") (pin "2") (pinfunction "2_2") (pintype "passive"))
      (node (ref "R51-1.2K") (pin "2") (pinfunction "2_2") (pintype "passive"))
      (node (ref "T1") (pin "1") (pinfunction "C_1") (pintype "passive"))
      (node (ref "T2") (pin "1") (pinfunction "C_1") (pintype "passive"))
      (node (ref "T3") (pin "1") (pinfunction "C_1") (pintype "passive"))
      (node (ref "U$5") (pin "VIN") (pinfunction "VIN_VIN") (pintype "bidirectional"))
      (node (ref "U2") (pin "1") (pinfunction "VSUP_1") (pintype "power_in"))
      (node (ref "U2") (pin "16") (pinfunction "DVDD_16") (pintype "power_in"))
      (node (ref "U3") (pin "1") (pinfunction "VSUP_1") (pintype "power_in"))
      (node (ref "U3") (pin "16") (pinfunction "DVDD_16") (pintype "power_in"))
      (node (ref "U4") (pin "1") (pinfunction "VSUP_1") (pintype "power_in"))
      (node (ref "U4") (pin "16") (pinfunction "DVDD_16") (pintype "power_in"))
    )
    (net (code "67") (name "Net-(T1-E)") (class "Default")
      (node (ref "CAP2") (pin "2") (pinfunction "2_2") (pintype "passive"))
      (node (ref "R4-20K3") (pin "1") (pinfunction "1_1") (pintype "passive"))
      (node (ref "T1") (pin "2") (pinfunction "E_2") (pintype "passive"))
      (node (ref "U2") (pin "3") (pinfunction "AVDD_3") (pintype "power_in"))
    )
    (net (code "68") (name "Net-(T2-B)") (class "Default")
      (node (ref "T2") (pin "3") (pinfunction "B_3") (pintype "passive"))
      (node (ref "U3") (pin "2") (pinfunction "BASE_2") (pintype "output"))
    )
    (net (code "69") (name "Net-(T2-E)") (class "Default")
      (node (ref "CAP7") (pin "2") (pinfunction "2_2") (pintype "passive"))
      (node (ref "R4-20K1") (pin "1") (pinfunction "1_1") (pintype "passive"))
      (node (ref "T2") (pin "2") (pinfunction "E_2") (pintype "passive"))
      (node (ref "U3") (pin "3") (pinfunction "AVDD_3") (pintype "power_in"))
    )
    (net (code "70") (name "Net-(T3-B)") (class "Default")
      (node (ref "T3") (pin "3") (pinfunction "B_3") (pintype "passive"))
      (node (ref "U4") (pin "2") (pinfunction "BASE_2") (pintype "output"))
    )
    (net (code "71") (name "Net-(T3-E)") (class "Default")
      (node (ref "CAP12") (pin "2") (pinfunction "2_2") (pintype "passive"))
      (node (ref "R4-20K2") (pin "1") (pinfunction "1_1") (pintype "passive"))
      (node (ref "T3") (pin "2") (pinfunction "E_2") (pintype "passive"))
      (node (ref "U4") (pin "3") (pinfunction "AVDD_3") (pintype "power_in"))
    )
    (net (code "72") (name "Net-(U$5-10-CS{slash}MQSR)") (class "Default")
      (node (ref "E-STOP") (pin "2") (pinfunction "2_2") (pintype "passive"))
      (node (ref "U$5") (pin "10-CS\\MQSR") (pinfunction "10-CS/MQSR_10-CS\\MQSR") (pintype "bidirectional"))
    )
    (net (code "73") (name "Net-(U2-INA+)") (class "Default")
      (node (ref "CAP4") (pin "2") (pinfunction "2_2") (pintype "passive"))
      (node (ref "R2-1K3") (pin "2") (pinfunction "2_2") (pintype "passive"))
      (node (ref "U2") (pin "8") (pinfunction "INA+_8") (pintype "input"))
    )
    (net (code "74") (name "Net-(U2-INB+)") (class "Default")
      (node (ref "CAP5") (pin "2") (pinfunction "2_2") (pintype "passive"))
      (node (ref "R1-1K3") (pin "2") (pinfunction "2_2") (pintype "passive"))
      (node (ref "U2") (pin "10") (pinfunction "INB+_10") (pintype "input"))
    )
    (net (code "75") (name "Net-(U2-RATE)") (class "Default")
      (node (ref "U2") (pin "14") (pinfunction "XI_14") (pintype "input"))
      (node (ref "U2") (pin "15") (pinfunction "RATE_15") (pintype "input"))
    )
    (net (code "76") (name "Net-(U2-VBG)") (class "Default")
      (node (ref "CAP3") (pin "2") (pinfunction "2_2") (pintype "passive"))
      (node (ref "U2") (pin "6") (pinfunction "VBG_6") (pintype "output"))
    )
    (net (code "77") (name "Net-(U2-VFB)") (class "Default")
      (node (ref "R3-8.2K3") (pin "2") (pinfunction "2_2") (pintype "passive"))
      (node (ref "R4-20K3") (pin "2") (pinfunction "2_2") (pintype "passive"))
      (node (ref "U2") (pin "4") (pinfunction "VFB_4") (pintype "input"))
    )
    (net (code "78") (name "Net-(U3-INA+)") (class "Default")
      (node (ref "CAP9") (pin "2") (pinfunction "2_2") (pintype "passive"))
      (node (ref "R2-1K1") (pin "2") (pinfunction "2_2") (pintype "passive"))
      (node (ref "U3") (pin "8") (pinfunction "INA+_8") (pintype "input"))
    )
    (net (code "79") (name "Net-(U3-INB+)") (class "Default")
      (node (ref "CAP10") (pin "2") (pinfunction "2_2") (pintype "passive"))
      (node (ref "R1-1K1") (pin "2") (pinfunction "2_2") (pintype "passive"))
      (node (ref "U3") (pin "10") (pinfunction "INB+_10") (pintype "input"))
    )
    (net (code "80") (name "Net-(U3-RATE)") (class "Default")
      (node (ref "U3") (pin "14") (pinfunction "XI_14") (pintype "input"))
      (node (ref "U3") (pin "15") (pinfunction "RATE_15") (pintype "input"))
    )
    (net (code "81") (name "Net-(U3-VBG)") (class "Default")
      (node (ref "CAP8") (pin "2") (pinfunction "2_2") (pintype "passive"))
      (node (ref "U3") (pin "6") (pinfunction "VBG_6") (pintype "output"))
    )
    (net (code "82") (name "Net-(U3-VFB)") (class "Default")
      (node (ref "R3-8.2K1") (pin "2") (pinfunction "2_2") (pintype "passive"))
      (node (ref "R4-20K1") (pin "2") (pinfunction "2_2") (pintype "passive"))
      (node (ref "U3") (pin "4") (pinfunction "VFB_4") (pintype "input"))
    )
    (net (code "83") (name "Net-(U4-INA+)") (class "Default")
      (node (ref "CAP14") (pin "2") (pinfunction "2_2") (pintype "passive"))
      (node (ref "R2-1K2") (pin "2") (pinfunction "2_2") (pintype "passive"))
      (node (ref "U4") (pin "8") (pinfunction "INA+_8") (pintype "input"))
    )
    (net (code "84") (name "Net-(U4-INB+)") (class "Default")
      (node (ref "CAP15") (pin "2") (pinfunction "2_2") (pintype "passive"))
      (node (ref "R1-1K2") (pin "2") (pinfunction "2_2") (pintype "passive"))
      (node (ref "U4") (pin "10") (pinfunction "INB+_10") (pintype "input"))
    )
    (net (code "85") (name "Net-(U4-RATE)") (class "Default")
      (node (ref "U4") (pin "14") (pinfunction "XI_14") (pintype "input"))
      (node (ref "U4") (pin "15") (pinfunction "RATE_15") (pintype "input"))
    )
    (net (code "86") (name "Net-(U4-VBG)") (class "Default")
      (node (ref "CAP13") (pin "2") (pinfunction "2_2") (pintype "passive"))
      (node (ref "U4") (pin "6") (pinfunction "VBG_6") (pintype "output"))
    )
    (net (code "87") (name "Net-(U4-VFB)") (class "Default")
      (node (ref "R3-8.2K2") (pin "2") (pinfunction "2_2") (pintype "passive"))
      (node (ref "R4-20K2") (pin "2") (pinfunction "2_2") (pintype "passive"))
      (node (ref "U4") (pin "4") (pinfunction "VFB_4") (pintype "input"))
    )
    (net (code "88") (name "unconnected-(12-5V-Pad1)") (class "Default")
      (node (ref "12-5V") (pin "1") (pinfunction "1_1") (pintype "passive"))
    )
    (net (code "89") (name "unconnected-(U$5-5V-Pad+5V)") (class "Default")
      (node (ref "U$5") (pin "+5V") (pinfunction "5V_+5V") (pintype "bidirectional"))
    )
    (net (code "90") (name "unconnected-(U$5-35{slash}TX8-Pad35-TX8)") (class "Default")
      (node (ref "U$5") (pin "35-TX8") (pinfunction "35/TX8_35-TX8") (pintype "bidirectional"))
    )
    (net (code "91") (name "unconnected-(U$5-Pad0-RX1{slash}CS1{slash}CRX2)") (class "Default")
      (node (ref "U$5") (pin "0-RX1/CS1/CRX2") (pinfunction "0-RX1/CS1/CRX2_0-RX1/CS1/CRX2") (pintype "bidirectional"))
    )
    (net (code "92") (name "unconnected-(U$5-Pad1-TX1{slash}MISO1{slash}CTX2)") (class "Default")
      (node (ref "U$5") (pin "1-TX1/MISO1/CTX2") (pinfunction "1-TX1/MISO1/CTX2_1-TX1/MISO1/CTX2") (pintype "bidirectional"))
    )
    (net (code "93") (name "unconnected-(U$5-Pad3V3-1)") (class "Default")
      (node (ref "U$5") (pin "3V3-1") (pinfunction "3V3-1_3V3-1") (pintype "bidirectional"))
    )
    (net (code "94") (name "unconnected-(U$5-Pad3V3-2)") (class "Default")
      (node (ref "U$5") (pin "3V3-2") (pinfunction "3V3-2_3V3-2") (pintype "bidirectional"))
    )
    (net (code "95") (name "unconnected-(U$5-Pad3V3-3)") (class "Default")
      (node (ref "U$5") (pin "3V3-3") (pinfunction "3V3-3_3V3-3") (pintype "bidirectional"))
    )
    (net (code "96") (name "unconnected-(U$5-Pad8-TX2{slash}IN1)") (class "Default")
      (node (ref "U$5") (pin "8-TX2/IN1") (pinfunction "8-TX2/IN1_8-TX2/IN1") (pintype "bidirectional"))
    )
    (net (code "97") (name "unconnected-(U$5-Pad11-MOSI{slash}CTX1)") (class "Default")
      (node (ref "U$5") (pin "11-MOSI/CTX1") (pinfunction "11-MOSI/CTX1_11-MOSI/CTX1") (pintype "bidirectional"))
    )
    (net (code "98") (name "unconnected-(U$5-Pad16-A2{slash}RX4{slash}SCL1)") (class "Default")
      (node (ref "U$5") (pin "16-A2/RX4/SCL1") (pinfunction "16-A2/RX4/SCL1_16-A2/RX4/SCL1") (pintype "bidirectional"))
    )
    (net (code "99") (name "unconnected-(U$5-Pad17-A3{slash}TX4{slash}SDA1)") (class "Default")
      (node (ref "U$5") (pin "17-A3/TX4/SDA1") (pinfunction "17-A3/TX4/SDA1_17-A3/TX4/SDA1") (pintype "bidirectional"))
    )
    (net (code "100") (name "unconnected-(U$5-Pad32-OUT1B)") (class "Default")
      (node (ref "U$5") (pin "32-OUT1B") (pinfunction "32-OUT1B_32-OUT1B") (pintype "bidirectional"))
    )
    (net (code "101") (name "unconnected-(U$5-Pad33-MCLK2)") (class "Default")
      (node (ref "U$5") (pin "33-MCLK2") (pinfunction "33-MCLK2_33-MCLK2") (pintype "bidirectional"))
    )
    (net (code "102") (name "unconnected-(U$5-Pad34-RX8)") (class "Default")
      (node (ref "U$5") (pin "34-RX8") (pinfunction "34-RX8_34-RX8") (pintype "bidirectional"))
    )
    (net (code "103") (name "unconnected-(U$5-Pad36-PWM)") (class "Default")
      (node (ref "U$5") (pin "36-PWM") (pinfunction "36-PWM_36-PWM") (pintype "bidirectional"))
    )
    (net (code "104") (name "unconnected-(U$5-Pad37-PWM)") (class "Default")
      (node (ref "U$5") (pin "37-PWM") (pinfunction "37-PWM_37-PWM") (pintype "bidirectional"))
    )
    (net (code "105") (name "unconnected-(U$5-Pad39-A15{slash}CS{slash}OUT1A)") (class "Default")
      (node (ref "U$5") (pin "39-A15/CS/OUT1A") (pinfunction "39-A15/CS/OUT1A_39-A15/CS/OUT1A") (pintype "bidirectional"))
    )
    (net (code "106") (name "unconnected-(U$5-PadD+)") (class "Default")
      (node (ref "U$5") (pin "D+") (pinfunction "D+_D+") (pintype "bidirectional"))
    )
    (net (code "107") (name "unconnected-(U$5-PadD-)") (class "Default")
      (node (ref "U$5") (pin "D-") (pinfunction "D-_D-") (pintype "bidirectional"))
    )
    (net (code "108") (name "unconnected-(U$5-PadDM)") (class "Default")
      (node (ref "U$5") (pin "DM") (pinfunction "DM_DM") (pintype "bidirectional"))
    )
    (net (code "109") (name "unconnected-(U$5-PadDP)") (class "Default")
      (node (ref "U$5") (pin "DP") (pinfunction "DP_DP") (pintype "bidirectional"))
    )
    (net (code "110") (name "unconnected-(U$5-PadG)") (class "Default")
      (node (ref "U$5") (pin "G") (pinfunction "G_G") (pintype "bidirectional"))
    )
    (net (code "111") (name "unconnected-(U$5-PadGND2)") (class "Default")
      (node (ref "U$5") (pin "GND2") (pinfunction "GND2_GND2") (pintype "bidirectional"))
    )
    (net (code "112") (name "unconnected-(U$5-PadGND4)") (class "Default")
      (node (ref "U$5") (pin "GND4") (pinfunction "GND4_GND4") (pintype "bidirectional"))
    )
    (net (code "113") (name "unconnected-(U$5-PadGND5)") (class "Default")
      (node (ref "U$5") (pin "GND5") (pinfunction "GND5_GND5") (pintype "bidirectional"))
    )
    (net (code "114") (name "unconnected-(U$5-PadLED)") (class "Default")
      (node (ref "U$5") (pin "LED") (pinfunction "LED_LED") (pintype "bidirectional"))
    )
    (net (code "115") (name "unconnected-(U$5-PadON{slash}OFF)") (class "Default")
      (node (ref "U$5") (pin "ON/OFF") (pinfunction "ON/OFF_ON/OFF") (pintype "bidirectional"))
    )
    (net (code "116") (name "unconnected-(U$5-PadPROGRAM)") (class "Default")
      (node (ref "U$5") (pin "PROGRAM") (pinfunction "PROGRAM_PROGRAM") (pintype "bidirectional"))
    )
    (net (code "117") (name "unconnected-(U$5-PadR+)") (class "Default")
      (node (ref "U$5") (pin "R+") (pinfunction "R+_R+") (pintype "bidirectional"))
    )
    (net (code "118") (name "unconnected-(U$5-PadR-)") (class "Default")
      (node (ref "U$5") (pin "R-") (pinfunction "R-_R-") (pintype "bidirectional"))
    )
    (net (code "119") (name "unconnected-(U$5-PadT+)") (class "Default")
      (node (ref "U$5") (pin "T+") (pinfunction "T+_T+") (pintype "bidirectional"))
    )
    (net (code "120") (name "unconnected-(U$5-PadT-)") (class "Default")
      (node (ref "U$5") (pin "T-") (pinfunction "T-_T-") (pintype "bidirectional"))
    )
    (net (code "121") (name "unconnected-(U$5-PadVBAT)") (class "Default")
      (node (ref "U$5") (pin "VBAT") (pinfunction "VBAT_VBAT") (pintype "bidirectional"))
    )
    (net (code "122") (name "unconnected-(U$5-PadVUSB)") (class "Default")
      (node (ref "U$5") (pin "VUSB") (pinfunction "VUSB_VUSB") (pintype "bidirectional"))
    )
    (net (code "123") (name "unconnected-(U2-XO-Pad13)") (class "Default")
      (node (ref "U2") (pin "13") (pinfunction "XO_13") (pintype "output"))
    )
    (net (code "124") (name "unconnected-(U3-XO-Pad13)") (class "Default")
      (node (ref "U3") (pin "13") (pinfunction "XO_13") (pintype "output"))
    )
    (net (code "125") (name "unconnected-(U4-XO-Pad13)") (class "Default")
      (node (ref "U4") (pin "13") (pinfunction "XO_13") (pintype "output"))
    )
  )
)
